# 555-ADSR-Rene-Schmitz.net
KiCad netlist of a schematic drawn in EAGLE
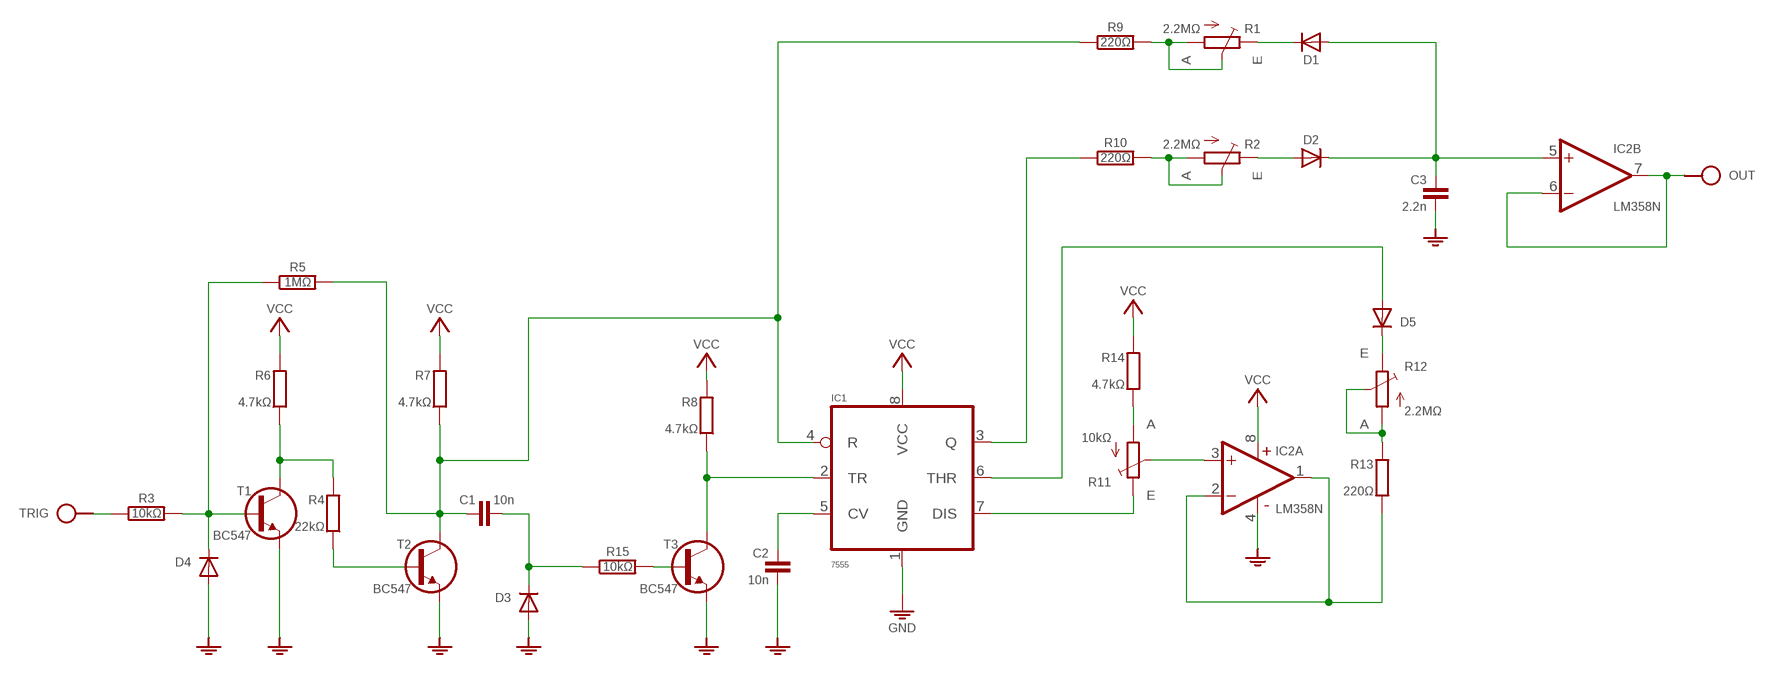
[diagram p0: schematic, sheet 1]

(export (version "E")
  (design (tool "Eeschema 10.0.6"))
  (components
    (comp (ref "C1")
      (value "10n")
      (footprint "eagle-import:C050-020X044")
      (libsource (lib "eagle-import") (part "C-H050-020X044"))
    )
    (comp (ref "C2")
      (value "10n")
      (footprint "eagle-import:C050-025X075_V")
      (libsource (lib "eagle-import") (part "C050-025X075/V"))
    )
    (comp (ref "C3")
      (value "2.2n")
      (footprint "eagle-import:C050-025X075_V")
      (libsource (lib "eagle-import") (part "C050-025X075/V"))
    )
    (comp (ref "D1")
      (value "DIODE-HDO34-7")
      (footprint "eagle-import:DO34-7")
      (libsource (lib "eagle-import") (part "DIODE-HDO34-7"))
    )
    (comp (ref "D2")
      (value "DIODE-HDO34-7")
      (footprint "eagle-import:DO34-7")
      (libsource (lib "eagle-import") (part "DIODE-HDO34-7"))
    )
    (comp (ref "D3")
      (value "DIODE34-7V")
      (footprint "eagle-import:DO34-7V")
      (libsource (lib "eagle-import") (part "DIODE34-7V"))
    )
    (comp (ref "D4")
      (value "DIODE34-7V")
      (footprint "eagle-import:DO34-7V")
      (libsource (lib "eagle-import") (part "DIODE34-7V"))
    )
    (comp (ref "D5")
      (value "DIODE34-7V")
      (footprint "eagle-import:DO34-7V")
      (libsource (lib "eagle-import") (part "DIODE34-7V"))
    )
    (comp (ref "IC1")
      (value "7555")
      (footprint "eagle-import:DIL08")
      (libsource (lib "eagle-import") (part "7555"))
    )
    (comp (ref "IC2")
      (value "LM358N")
      (footprint "eagle-import:DIL08")
      (libsource (lib "eagle-import") (part "LM358N"))
    )
    (comp (ref "OUT")
      (value "SPAD")
      (footprint "eagle-import:SPAD")
      (libsource (lib "eagle-import") (part "SPAD"))
    )
    (comp (ref "R1")
      (value "2.2MΩ")
      (footprint "eagle-import:R-TRIM")
      (libsource (lib "eagle-import") (part "TRIMR-TRIM"))
    )
    (comp (ref "R2")
      (value "2.2MΩ")
      (footprint "eagle-import:R-TRIM")
      (libsource (lib "eagle-import") (part "TRIMR-TRIM"))
    )
    (comp (ref "R3")
      (value "10kΩ")
      (footprint "eagle-import:0204_10")
      (libsource (lib "eagle-import") (part "R-H0204/10"))
    )
    (comp (ref "R4")
      (value "22kΩ")
      (footprint "eagle-import:0204_10-V")
      (libsource (lib "eagle-import") (part "R0204/10-V"))
    )
    (comp (ref "R5")
      (value "1MΩ")
      (footprint "eagle-import:0204_10")
      (libsource (lib "eagle-import") (part "R-H0204/10"))
    )
    (comp (ref "R6")
      (value "4.7kΩ")
      (footprint "eagle-import:0204_10")
      (libsource (lib "eagle-import") (part "R0204/10"))
    )
    (comp (ref "R7")
      (value "4.7kΩ")
      (footprint "eagle-import:0204_10")
      (libsource (lib "eagle-import") (part "R0204/10"))
    )
    (comp (ref "R8")
      (value "4.7kΩ")
      (footprint "eagle-import:0204_10")
      (libsource (lib "eagle-import") (part "R0204/10"))
    )
    (comp (ref "R9")
      (value "220Ω")
      (footprint "eagle-import:0204_10")
      (libsource (lib "eagle-import") (part "R-H0204/10"))
    )
    (comp (ref "R10")
      (value "220Ω")
      (footprint "eagle-import:0204_10")
      (libsource (lib "eagle-import") (part "R-H0204/10"))
    )
    (comp (ref "R11")
      (value "10kΩ")
      (footprint "eagle-import:R-TRIM")
      (libsource (lib "eagle-import") (part "TRIMR-TRIM"))
    )
    (comp (ref "R12")
      (value "2.2MΩ")
      (footprint "eagle-import:R-TRIM")
      (libsource (lib "eagle-import") (part "TRIMR-TRIM"))
    )
    (comp (ref "R13")
      (value "220Ω")
      (footprint "eagle-import:0204_10-V")
      (libsource (lib "eagle-import") (part "R0204/10-V"))
    )
    (comp (ref "R14")
      (value "4.7kΩ")
      (footprint "eagle-import:0204_10")
      (libsource (lib "eagle-import") (part "R0204/10"))
    )
    (comp (ref "R15")
      (value "10kΩ")
      (footprint "eagle-import:0204_10")
      (libsource (lib "eagle-import") (part "R-H0204/10"))
    )
    (comp (ref "S2")
      (value "VCC_GNDL")
      (footprint "eagle-import:SPAD-+")
      (libsource (lib "eagle-import") (part "VCC_GNDL"))
    )
    (comp (ref "T1")
      (value "BC547")
      (footprint "eagle-import:TO92-CBE")
      (libsource (lib "eagle-import") (part "BC547"))
    )
    (comp (ref "T2")
      (value "BC547")
      (footprint "eagle-import:TO92-CBE")
      (libsource (lib "eagle-import") (part "BC547"))
    )
    (comp (ref "T3")
      (value "BC547")
      (footprint "eagle-import:TO92-CBE")
      (libsource (lib "eagle-import") (part "BC547"))
    )
    (comp (ref "TRIG")
      (value "SPAD")
      (footprint "eagle-import:SPAD")
      (libsource (lib "eagle-import") (part "SPAD"))
    )
  )
  (nets
    (net (code "1") (name "GND") (class "Default")
      (node (ref "C2") (pin "2") (pinfunction "2_2") (pintype "passive"))
      (node (ref "C3") (pin "2") (pinfunction "2_2") (pintype "passive"))
      (node (ref "D3") (pin "A") (pinfunction "A_A") (pintype "passive"))
      (node (ref "D4") (pin "A") (pinfunction "A_A") (pintype "passive"))
      (node (ref "IC1") (pin "1") (pinfunction "GND_1") (pintype "power_in"))
      (node (ref "IC2") (pin "4") (pinfunction "V-_4") (pintype "power_in"))
      (node (ref "S2") (pin "1") (pinfunction "GND_1") (pintype "power_in"))
      (node (ref "T1") (pin "E") (pinfunction "E_E") (pintype "passive"))
      (node (ref "T2") (pin "E") (pinfunction "E_E") (pintype "passive"))
      (node (ref "T3") (pin "E") (pinfunction "E_E") (pintype "passive"))
    )
    (net (code "2") (name "Net-(C1-Pad2)") (class "Default")
      (node (ref "C1") (pin "2") (pinfunction "2_2") (pintype "passive"))
      (node (ref "D3") (pin "C") (pinfunction "C_C") (pintype "passive"))
      (node (ref "R15") (pin "1") (pinfunction "1_1") (pintype "passive"))
    )
    (net (code "3") (name "Net-(D4-PadC)") (class "Default")
      (node (ref "D4") (pin "C") (pinfunction "C_C") (pintype "passive"))
      (node (ref "R3") (pin "2") (pinfunction "2_2") (pintype "passive"))
      (node (ref "R5") (pin "1") (pinfunction "1_1") (pintype "passive"))
      (node (ref "T1") (pin "B") (pinfunction "B_B") (pintype "passive"))
    )
    (net (code "4") (name "Net-(IC1-CV)") (class "Default")
      (node (ref "C2") (pin "1") (pinfunction "1_1") (pintype "passive"))
      (node (ref "IC1") (pin "5") (pinfunction "CV_5") (pintype "input"))
    )
    (net (code "5") (name "Net-(IC1-DIS)") (class "Default")
      (node (ref "IC1") (pin "7") (pinfunction "DIS_7") (pintype "passive"))
      (node (ref "R11") (pin "3") (pinfunction "E_3") (pintype "passive"))
    )
    (net (code "6") (name "Net-(IC1-Q)") (class "Default")
      (node (ref "IC1") (pin "3") (pinfunction "Q_3") (pintype "output"))
      (node (ref "R10") (pin "1") (pinfunction "1_1") (pintype "passive"))
    )
    (net (code "7") (name "Net-(IC1-R)") (class "Default")
      (node (ref "C1") (pin "1") (pinfunction "1_1") (pintype "passive"))
      (node (ref "IC1") (pin "4") (pinfunction "R_4") (pintype "input"))
      (node (ref "R5") (pin "2") (pinfunction "2_2") (pintype "passive"))
      (node (ref "R7") (pin "2") (pinfunction "2_2") (pintype "passive"))
      (node (ref "R9") (pin "1") (pinfunction "1_1") (pintype "passive"))
      (node (ref "T2") (pin "C") (pinfunction "C_C") (pintype "passive"))
    )
    (net (code "8") (name "Net-(IC1-THR)") (class "Default")
      (node (ref "D5") (pin "A") (pinfunction "A_A") (pintype "passive"))
      (node (ref "IC1") (pin "6") (pinfunction "THR_6") (pintype "input"))
    )
    (net (code "9") (name "Net-(IC1-TR)") (class "Default")
      (node (ref "IC1") (pin "2") (pinfunction "TR_2") (pintype "input"))
      (node (ref "R8") (pin "2") (pinfunction "2_2") (pintype "passive"))
      (node (ref "T3") (pin "C") (pinfunction "C_C") (pintype "passive"))
    )
    (net (code "10") (name "Net-(IC2A-+IN)") (class "Default")
      (node (ref "IC2") (pin "3") (pinfunction "+IN_3") (pintype "input"))
      (node (ref "R11") (pin "2") (pinfunction "S_2") (pintype "passive"))
    )
    (net (code "11") (name "Net-(IC2A--IN)") (class "Default")
      (node (ref "IC2") (pin "1") (pinfunction "OUT_1") (pintype "output"))
      (node (ref "IC2") (pin "2") (pinfunction "-IN_2") (pintype "input"))
      (node (ref "R13") (pin "2") (pinfunction "2_2") (pintype "passive"))
    )
    (net (code "12") (name "Net-(IC2B-+IN)") (class "Default")
      (node (ref "C3") (pin "1") (pinfunction "1_1") (pintype "passive"))
      (node (ref "D1") (pin "A") (pinfunction "A_A") (pintype "passive"))
      (node (ref "D2") (pin "C") (pinfunction "C_C") (pintype "passive"))
      (node (ref "IC2") (pin "5") (pinfunction "+IN_5") (pintype "input"))
    )
    (net (code "13") (name "Net-(IC2B--IN)") (class "Default")
      (node (ref "IC2") (pin "6") (pinfunction "-IN_6") (pintype "input"))
      (node (ref "IC2") (pin "7") (pinfunction "OUT_7") (pintype "output"))
      (node (ref "OUT") (pin "1") (pinfunction "P$1_1") (pintype "passive"))
    )
    (net (code "14") (name "Net-(R1-A)") (class "Default")
      (node (ref "R1") (pin "1") (pinfunction "A_1") (pintype "passive"))
      (node (ref "R1") (pin "2") (pinfunction "S_2") (pintype "passive"))
      (node (ref "R9") (pin "2") (pinfunction "2_2") (pintype "passive"))
    )
    (net (code "15") (name "Net-(R1-E)") (class "Default")
      (node (ref "D1") (pin "C") (pinfunction "C_C") (pintype "passive"))
      (node (ref "R1") (pin "3") (pinfunction "E_3") (pintype "passive"))
    )
    (net (code "16") (name "Net-(R2-A)") (class "Default")
      (node (ref "R10") (pin "2") (pinfunction "2_2") (pintype "passive"))
      (node (ref "R2") (pin "1") (pinfunction "A_1") (pintype "passive"))
      (node (ref "R2") (pin "2") (pinfunction "S_2") (pintype "passive"))
    )
    (net (code "17") (name "Net-(R2-E)") (class "Default")
      (node (ref "D2") (pin "A") (pinfunction "A_A") (pintype "passive"))
      (node (ref "R2") (pin "3") (pinfunction "E_3") (pintype "passive"))
    )
    (net (code "18") (name "Net-(R4-Pad1)") (class "Default")
      (node (ref "R4") (pin "1") (pinfunction "1_1") (pintype "passive"))
      (node (ref "R6") (pin "2") (pinfunction "2_2") (pintype "passive"))
      (node (ref "T1") (pin "C") (pinfunction "C_C") (pintype "passive"))
    )
    (net (code "19") (name "Net-(R4-Pad2)") (class "Default")
      (node (ref "R4") (pin "2") (pinfunction "2_2") (pintype "passive"))
      (node (ref "T2") (pin "B") (pinfunction "B_B") (pintype "passive"))
    )
    (net (code "20") (name "Net-(R11-A)") (class "Default")
      (node (ref "R11") (pin "1") (pinfunction "A_1") (pintype "passive"))
      (node (ref "R14") (pin "2") (pinfunction "2_2") (pintype "passive"))
    )
    (net (code "21") (name "Net-(R12-A)") (class "Default")
      (node (ref "R12") (pin "1") (pinfunction "A_1") (pintype "passive"))
      (node (ref "R12") (pin "2") (pinfunction "S_2") (pintype "passive"))
      (node (ref "R13") (pin "1") (pinfunction "1_1") (pintype "passive"))
    )
    (net (code "22") (name "Net-(R12-E)") (class "Default")
      (node (ref "D5") (pin "C") (pinfunction "C_C") (pintype "passive"))
      (node (ref "R12") (pin "3") (pinfunction "E_3") (pintype "passive"))
    )
    (net (code "23") (name "Net-(R15-Pad2)") (class "Default")
      (node (ref "R15") (pin "2") (pinfunction "2_2") (pintype "passive"))
      (node (ref "T3") (pin "B") (pinfunction "B_B") (pintype "passive"))
    )
    (net (code "24") (name "Net-(TRIG-P$1)") (class "Default")
      (node (ref "R3") (pin "1") (pinfunction "1_1") (pintype "passive"))
      (node (ref "TRIG") (pin "1") (pinfunction "P$1_1") (pintype "passive"))
    )
    (net (code "25") (name "VCC") (class "Default")
      (node (ref "IC1") (pin "8") (pinfunction "VCC_8") (pintype "power_in"))
      (node (ref "IC2") (pin "8") (pinfunction "V+_8") (pintype "power_in"))
      (node (ref "R14") (pin "1") (pinfunction "1_1") (pintype "passive"))
      (node (ref "R6") (pin "1") (pinfunction "1_1") (pintype "passive"))
      (node (ref "R7") (pin "1") (pinfunction "1_1") (pintype "passive"))
      (node (ref "R8") (pin "1") (pinfunction "1_1") (pintype "passive"))
      (node (ref "S2") (pin "2") (pinfunction "VCC_2") (pintype "power_in"))
    )
  )
)
